# AD595_thermocouple_breakout_board.net
KiCad netlist of a schematic drawn in EAGLE
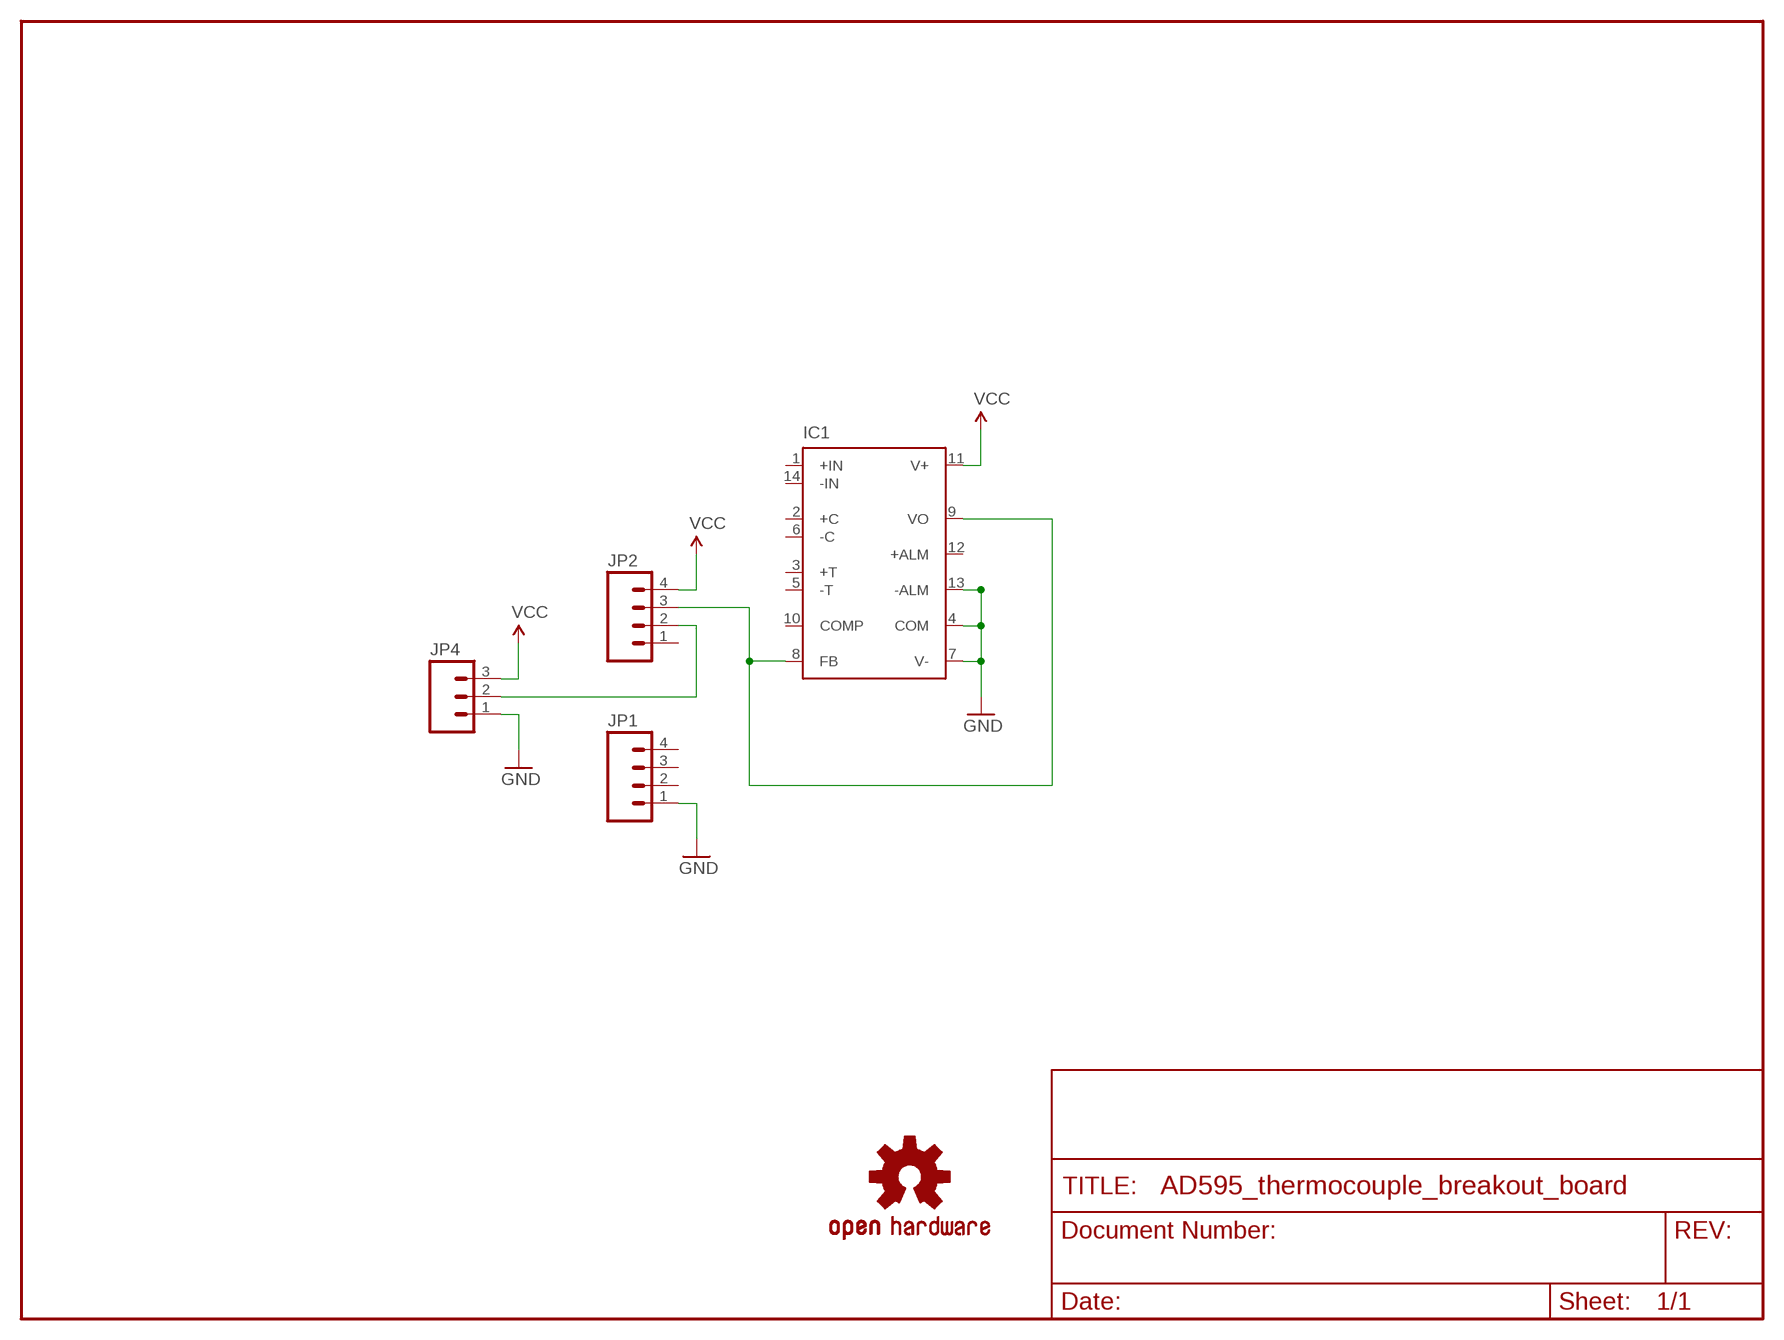
[diagram p0: schematic, sheet 1]

(export (version "E")
  (design (tool "Eeschema 10.0.6"))
  (components
    (comp (ref "IC1")
      (value "AD595")
      (footprint "eagle-import:DIL14")
      (fields (field (name "MPN") "AD595AQ"))
      (libsource (lib "eagle-import") (part "AD595"))
    )
    (comp (ref "JP1")
      (value "M04LOCK")
      (footprint "eagle-import:1X04_LOCK")
      (libsource (lib "eagle-import") (part "M04LOCK"))
    )
    (comp (ref "JP2")
      (value "M04LOCK")
      (footprint "eagle-import:1X04_LOCK")
      (libsource (lib "eagle-import") (part "M04LOCK"))
    )
    (comp (ref "JP4")
      (value "M03LOCK")
      (footprint "eagle-import:1X03_LOCK")
      (libsource (lib "eagle-import") (part "M03LOCK"))
    )
    (comp (ref "U$1")
      (value "OSHW-LOGOS")
      (footprint "eagle-import:OSHW-LOGO-S")
      (libsource (lib "eagle-import") (part "OSHW-LOGOS"))
    )
  )
  (nets
    (net (code "1") (name "GND") (class "Default")
      (node (ref "IC1") (pin "13") (pinfunction "-ALM_13") (pintype "passive"))
      (node (ref "IC1") (pin "4") (pinfunction "COM_4") (pintype "power_in"))
      (node (ref "IC1") (pin "7") (pinfunction "V-_7") (pintype "power_in"))
      (node (ref "JP1") (pin "1") (pinfunction "1_1") (pintype "passive"))
      (node (ref "JP4") (pin "1") (pinfunction "1_1") (pintype "passive"))
    )
    (net (code "2") (name "Net-(IC1-FB)") (class "Default")
      (node (ref "IC1") (pin "8") (pinfunction "FB_8") (pintype "passive"))
      (node (ref "IC1") (pin "9") (pinfunction "VO_9") (pintype "output"))
      (node (ref "JP2") (pin "3") (pinfunction "3_3") (pintype "passive"))
    )
    (net (code "3") (name "Net-(JP2-Pad2)") (class "Default")
      (node (ref "JP2") (pin "2") (pinfunction "2_2") (pintype "passive"))
      (node (ref "JP4") (pin "2") (pinfunction "2_2") (pintype "passive"))
    )
    (net (code "4") (name "VCC") (class "Default")
      (node (ref "IC1") (pin "11") (pinfunction "V+_11") (pintype "power_in"))
      (node (ref "JP2") (pin "4") (pinfunction "4_4") (pintype "passive"))
      (node (ref "JP4") (pin "3") (pinfunction "3_3") (pintype "passive"))
    )
    (net (code "5") (name "unconnected-(IC1-+ALM-Pad12)") (class "Default")
      (node (ref "IC1") (pin "12") (pinfunction "+ALM_12") (pintype "passive"))
    )
    (net (code "6") (name "unconnected-(IC1-+C-Pad2)") (class "Default")
      (node (ref "IC1") (pin "2") (pinfunction "+C_2") (pintype "input"))
    )
    (net (code "7") (name "unconnected-(IC1-+IN-Pad1)") (class "Default")
      (node (ref "IC1") (pin "1") (pinfunction "+IN_1") (pintype "input"))
    )
    (net (code "8") (name "unconnected-(IC1-+T-Pad3)") (class "Default")
      (node (ref "IC1") (pin "3") (pinfunction "+T_3") (pintype "passive"))
    )
    (net (code "9") (name "unconnected-(IC1--C-Pad6)") (class "Default")
      (node (ref "IC1") (pin "6") (pinfunction "-C_6") (pintype "input"))
    )
    (net (code "10") (name "unconnected-(IC1--IN-Pad14)") (class "Default")
      (node (ref "IC1") (pin "14") (pinfunction "-IN_14") (pintype "input"))
    )
    (net (code "11") (name "unconnected-(IC1--T-Pad5)") (class "Default")
      (node (ref "IC1") (pin "5") (pinfunction "-T_5") (pintype "passive"))
    )
    (net (code "12") (name "unconnected-(IC1-COMP-Pad10)") (class "Default")
      (node (ref "IC1") (pin "10") (pinfunction "COMP_10") (pintype "passive"))
    )
    (net (code "13") (name "unconnected-(JP1-Pad2)") (class "Default")
      (node (ref "JP1") (pin "2") (pinfunction "2_2") (pintype "passive"))
    )
    (net (code "14") (name "unconnected-(JP1-Pad3)") (class "Default")
      (node (ref "JP1") (pin "3") (pinfunction "3_3") (pintype "passive"))
    )
    (net (code "15") (name "unconnected-(JP1-Pad4)") (class "Default")
      (node (ref "JP1") (pin "4") (pinfunction "4_4") (pintype "passive"))
    )
    (net (code "16") (name "unconnected-(JP2-Pad1)") (class "Default")
      (node (ref "JP2") (pin "1") (pinfunction "1_1") (pintype "passive"))
    )
  )
)
